# RB02.net
KiCad netlist of a schematic drawn in EAGLE
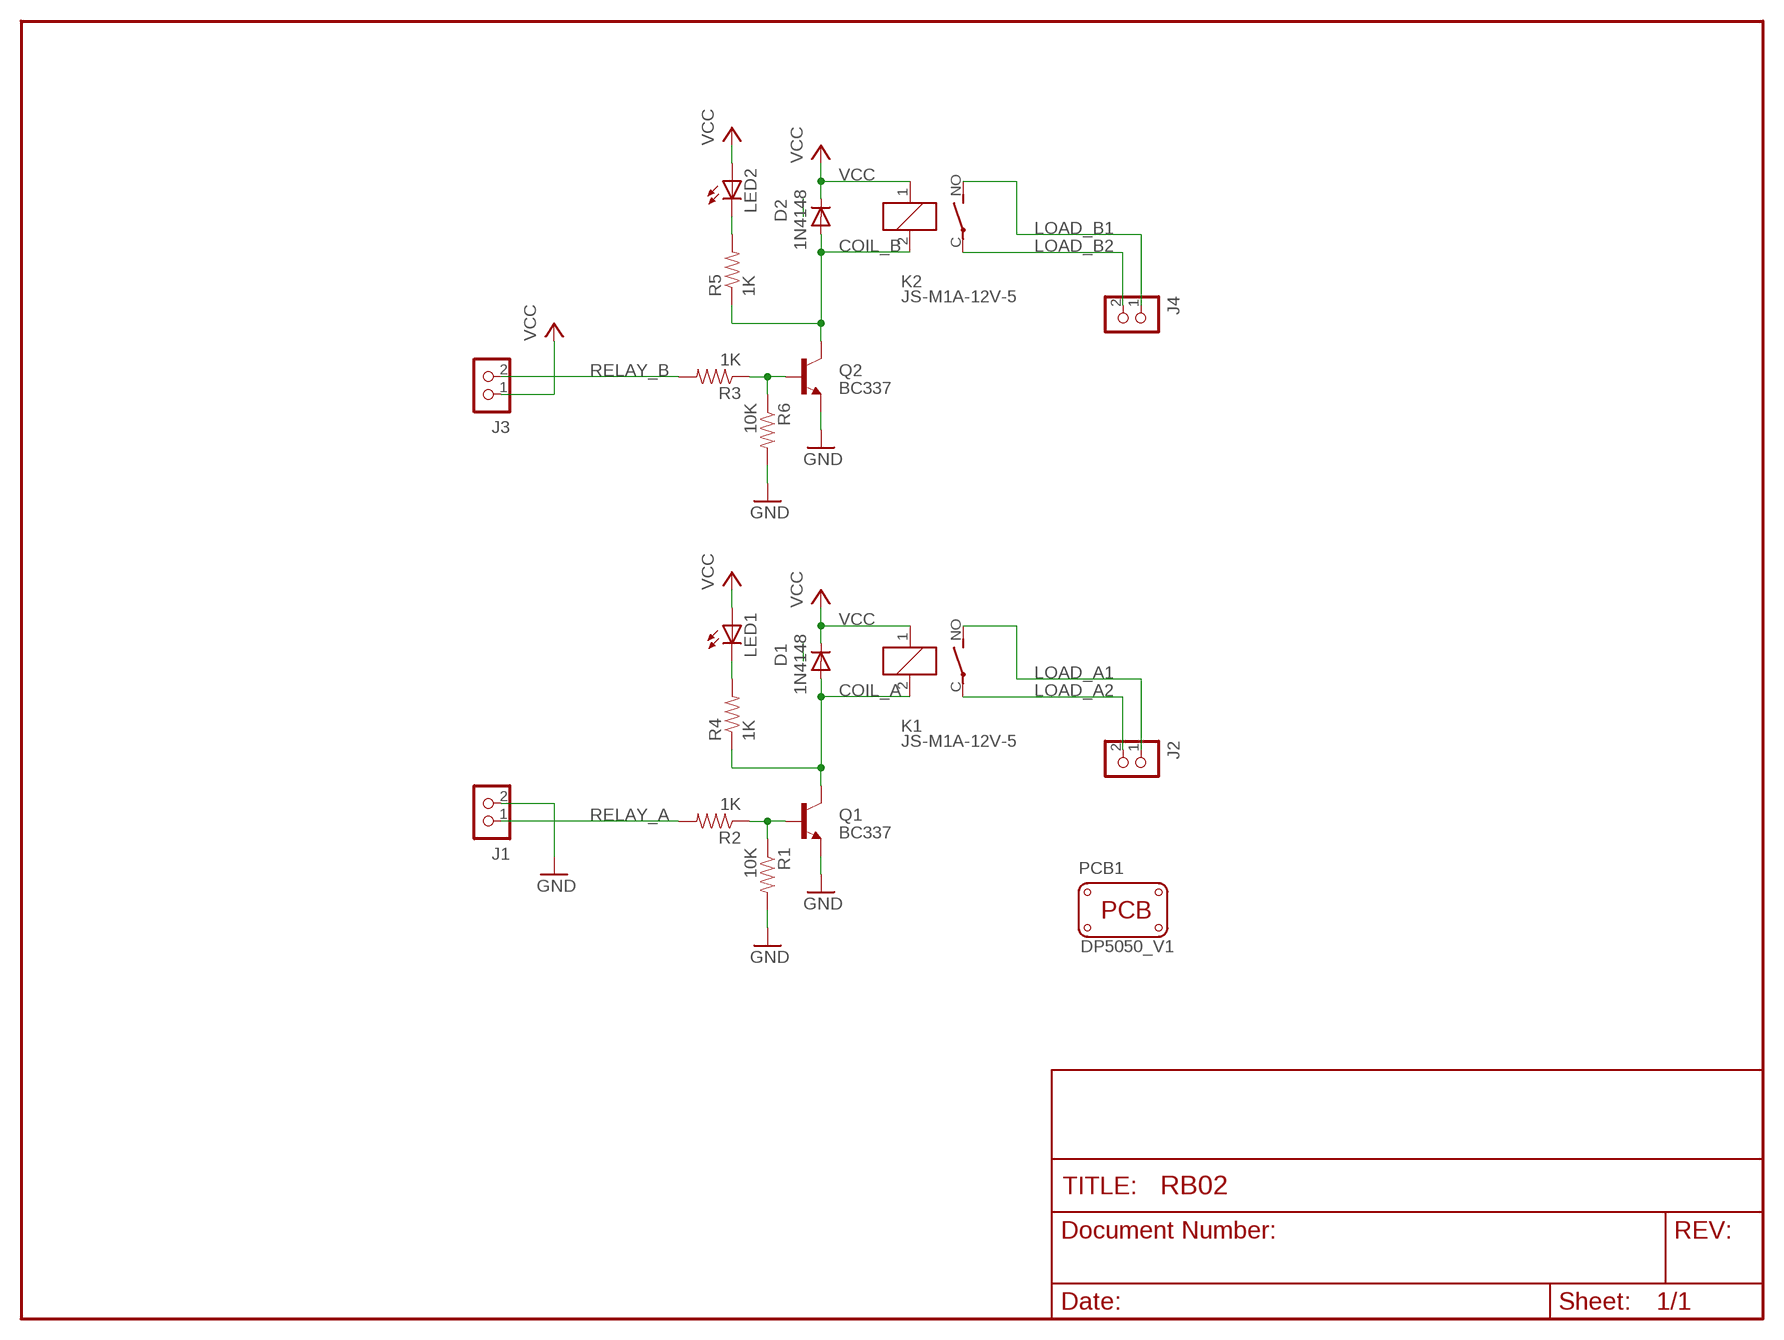
[diagram p0: schematic, sheet 1]

(export (version "E")
  (design (tool "Eeschema 10.0.6"))
  (components
    (comp (ref "D1")
      (value "1N4148")
      (footprint "eagle-import:DIODE-1N4148")
      (libsource (lib "eagle-import") (part "DIODE1N4148"))
    )
    (comp (ref "D2")
      (value "1N4148")
      (footprint "eagle-import:DIODE-1N4148")
      (libsource (lib "eagle-import") (part "DIODE1N4148"))
    )
    (comp (ref "J1")
      (value "CON_TERMINAL_BLOCK_02-5MM")
      (footprint "eagle-import:TERMINAL_BLOCK_2P_5")
      (libsource (lib "eagle-import") (part "CON_TERMINAL_BLOCK_02-5MM"))
    )
    (comp (ref "J2")
      (value "CON_TERMINAL_BLOCK_02-5MM")
      (footprint "eagle-import:TERMINAL_BLOCK_2P_5")
      (libsource (lib "eagle-import") (part "CON_TERMINAL_BLOCK_02-5MM"))
    )
    (comp (ref "J3")
      (value "CON_TERMINAL_BLOCK_02-5MM")
      (footprint "eagle-import:TERMINAL_BLOCK_2P_5")
      (libsource (lib "eagle-import") (part "CON_TERMINAL_BLOCK_02-5MM"))
    )
    (comp (ref "J4")
      (value "CON_TERMINAL_BLOCK_02-5MM")
      (footprint "eagle-import:TERMINAL_BLOCK_2P_5")
      (libsource (lib "eagle-import") (part "CON_TERMINAL_BLOCK_02-5MM"))
    )
    (comp (ref "K1")
      (value "JS-M1A-12V-5")
      (footprint "eagle-import:JS-M1A")
      (fields (field (name "MPN") "JSM1A-12V-5"))
      (libsource (lib "eagle-import") (part "JS-M1A-12V-5"))
    )
    (comp (ref "K2")
      (value "JS-M1A-12V-5")
      (footprint "eagle-import:JS-M1A")
      (fields (field (name "MPN") "JSM1A-12V-5"))
      (libsource (lib "eagle-import") (part "JS-M1A-12V-5"))
    )
    (comp (ref "LED1")
      (value "LED5MM")
      (footprint "eagle-import:LED5MM")
      (libsource (lib "eagle-import") (part "LED5MM"))
    )
    (comp (ref "LED2")
      (value "LED5MM")
      (footprint "eagle-import:LED5MM")
      (libsource (lib "eagle-import") (part "LED5MM"))
    )
    (comp (ref "PCB1")
      (value "PCB_DP_SQUARE-5X5")
      (footprint "eagle-import:DP5050_V1")
      (libsource (lib "eagle-import") (part "PCB_DP_SQUARE-5X5"))
    )
    (comp (ref "Q1")
      (value "BC337")
      (footprint "eagle-import:TO92")
      (libsource (lib "eagle-import") (part "BC337"))
    )
    (comp (ref "Q2")
      (value "BC337")
      (footprint "eagle-import:TO92")
      (libsource (lib "eagle-import") (part "BC337"))
    )
    (comp (ref "R1")
      (value "10K")
      (footprint "eagle-import:AXIAL-0.3")
      (libsource (lib "eagle-import") (part "RESISTORAXIAL-0.3"))
    )
    (comp (ref "R2")
      (value "1K")
      (footprint "eagle-import:AXIAL-0.3")
      (libsource (lib "eagle-import") (part "RESISTORAXIAL-0.3"))
    )
    (comp (ref "R3")
      (value "1K")
      (footprint "eagle-import:AXIAL-0.3")
      (libsource (lib "eagle-import") (part "RESISTORAXIAL-0.3"))
    )
    (comp (ref "R4")
      (value "1K")
      (footprint "eagle-import:AXIAL-0.3")
      (libsource (lib "eagle-import") (part "RESISTORAXIAL-0.3"))
    )
    (comp (ref "R5")
      (value "1K")
      (footprint "eagle-import:AXIAL-0.3")
      (libsource (lib "eagle-import") (part "RESISTORAXIAL-0.3"))
    )
    (comp (ref "R6")
      (value "10K")
      (footprint "eagle-import:AXIAL-0.3")
      (libsource (lib "eagle-import") (part "RESISTORAXIAL-0.3"))
    )
  )
  (nets
    (net (code "1") (name "/COIL_A") (class "Default")
      (node (ref "D1") (pin "A") (pinfunction "A_A") (pintype "passive"))
      (node (ref "K1") (pin "2") (pinfunction "2_2") (pintype "passive"))
      (node (ref "Q1") (pin "3") (pinfunction "C_3") (pintype "passive"))
      (node (ref "R4") (pin "P$1") (pinfunction "1_P$1") (pintype "passive"))
    )
    (net (code "2") (name "/COIL_B") (class "Default")
      (node (ref "D2") (pin "A") (pinfunction "A_A") (pintype "passive"))
      (node (ref "K2") (pin "2") (pinfunction "2_2") (pintype "passive"))
      (node (ref "Q2") (pin "3") (pinfunction "C_3") (pintype "passive"))
      (node (ref "R5") (pin "P$1") (pinfunction "1_P$1") (pintype "passive"))
    )
    (net (code "3") (name "/LOAD_A1") (class "Default")
      (node (ref "J2") (pin "1") (pinfunction "1_1") (pintype "passive"))
      (node (ref "K1") (pin "NO") (pinfunction "S_NO") (pintype "passive"))
    )
    (net (code "4") (name "/LOAD_A2") (class "Default")
      (node (ref "J2") (pin "2") (pinfunction "2_2") (pintype "passive"))
      (node (ref "K1") (pin "C") (pinfunction "P_C") (pintype "passive"))
    )
    (net (code "5") (name "/LOAD_B1") (class "Default")
      (node (ref "J4") (pin "1") (pinfunction "1_1") (pintype "passive"))
      (node (ref "K2") (pin "NO") (pinfunction "S_NO") (pintype "passive"))
    )
    (net (code "6") (name "/LOAD_B2") (class "Default")
      (node (ref "J4") (pin "2") (pinfunction "2_2") (pintype "passive"))
      (node (ref "K2") (pin "C") (pinfunction "P_C") (pintype "passive"))
    )
    (net (code "7") (name "/RELAY_A") (class "Default")
      (node (ref "J1") (pin "1") (pinfunction "1_1") (pintype "passive"))
      (node (ref "R2") (pin "P$2") (pinfunction "2_P$2") (pintype "passive"))
    )
    (net (code "8") (name "/RELAY_B") (class "Default")
      (node (ref "J3") (pin "2") (pinfunction "2_2") (pintype "passive"))
      (node (ref "R3") (pin "P$2") (pinfunction "2_P$2") (pintype "passive"))
    )
    (net (code "9") (name "GND") (class "Default")
      (node (ref "J1") (pin "2") (pinfunction "2_2") (pintype "passive"))
      (node (ref "Q1") (pin "1") (pinfunction "E_1") (pintype "passive"))
      (node (ref "Q2") (pin "1") (pinfunction "E_1") (pintype "passive"))
      (node (ref "R1") (pin "P$2") (pinfunction "2_P$2") (pintype "passive"))
      (node (ref "R6") (pin "P$2") (pinfunction "2_P$2") (pintype "passive"))
    )
    (net (code "10") (name "Net-(LED1-C)") (class "Default")
      (node (ref "LED1") (pin "K") (pinfunction "C_K") (pintype "passive"))
      (node (ref "R4") (pin "P$2") (pinfunction "2_P$2") (pintype "passive"))
    )
    (net (code "11") (name "Net-(LED2-C)") (class "Default")
      (node (ref "LED2") (pin "K") (pinfunction "C_K") (pintype "passive"))
      (node (ref "R5") (pin "P$2") (pinfunction "2_P$2") (pintype "passive"))
    )
    (net (code "12") (name "Net-(Q1-B)") (class "Default")
      (node (ref "Q1") (pin "2") (pinfunction "B_2") (pintype "passive"))
      (node (ref "R1") (pin "P$1") (pinfunction "1_P$1") (pintype "passive"))
      (node (ref "R2") (pin "P$1") (pinfunction "1_P$1") (pintype "passive"))
    )
    (net (code "13") (name "Net-(Q2-B)") (class "Default")
      (node (ref "Q2") (pin "2") (pinfunction "B_2") (pintype "passive"))
      (node (ref "R3") (pin "P$1") (pinfunction "1_P$1") (pintype "passive"))
      (node (ref "R6") (pin "P$1") (pinfunction "1_P$1") (pintype "passive"))
    )
    (net (code "14") (name "VCC") (class "Default")
      (node (ref "D1") (pin "C") (pinfunction "C_C") (pintype "passive"))
      (node (ref "D2") (pin "C") (pinfunction "C_C") (pintype "passive"))
      (node (ref "J3") (pin "1") (pinfunction "1_1") (pintype "passive"))
      (node (ref "K1") (pin "1") (pinfunction "1_1") (pintype "passive"))
      (node (ref "K2") (pin "1") (pinfunction "1_1") (pintype "passive"))
      (node (ref "LED1") (pin "A") (pinfunction "A_A") (pintype "passive"))
      (node (ref "LED2") (pin "A") (pinfunction "A_A") (pintype "passive"))
    )
  )
)
